# 3_waffling60-NMB_mcu.net
KiCad netlist of a schematic drawn in Altium Designer
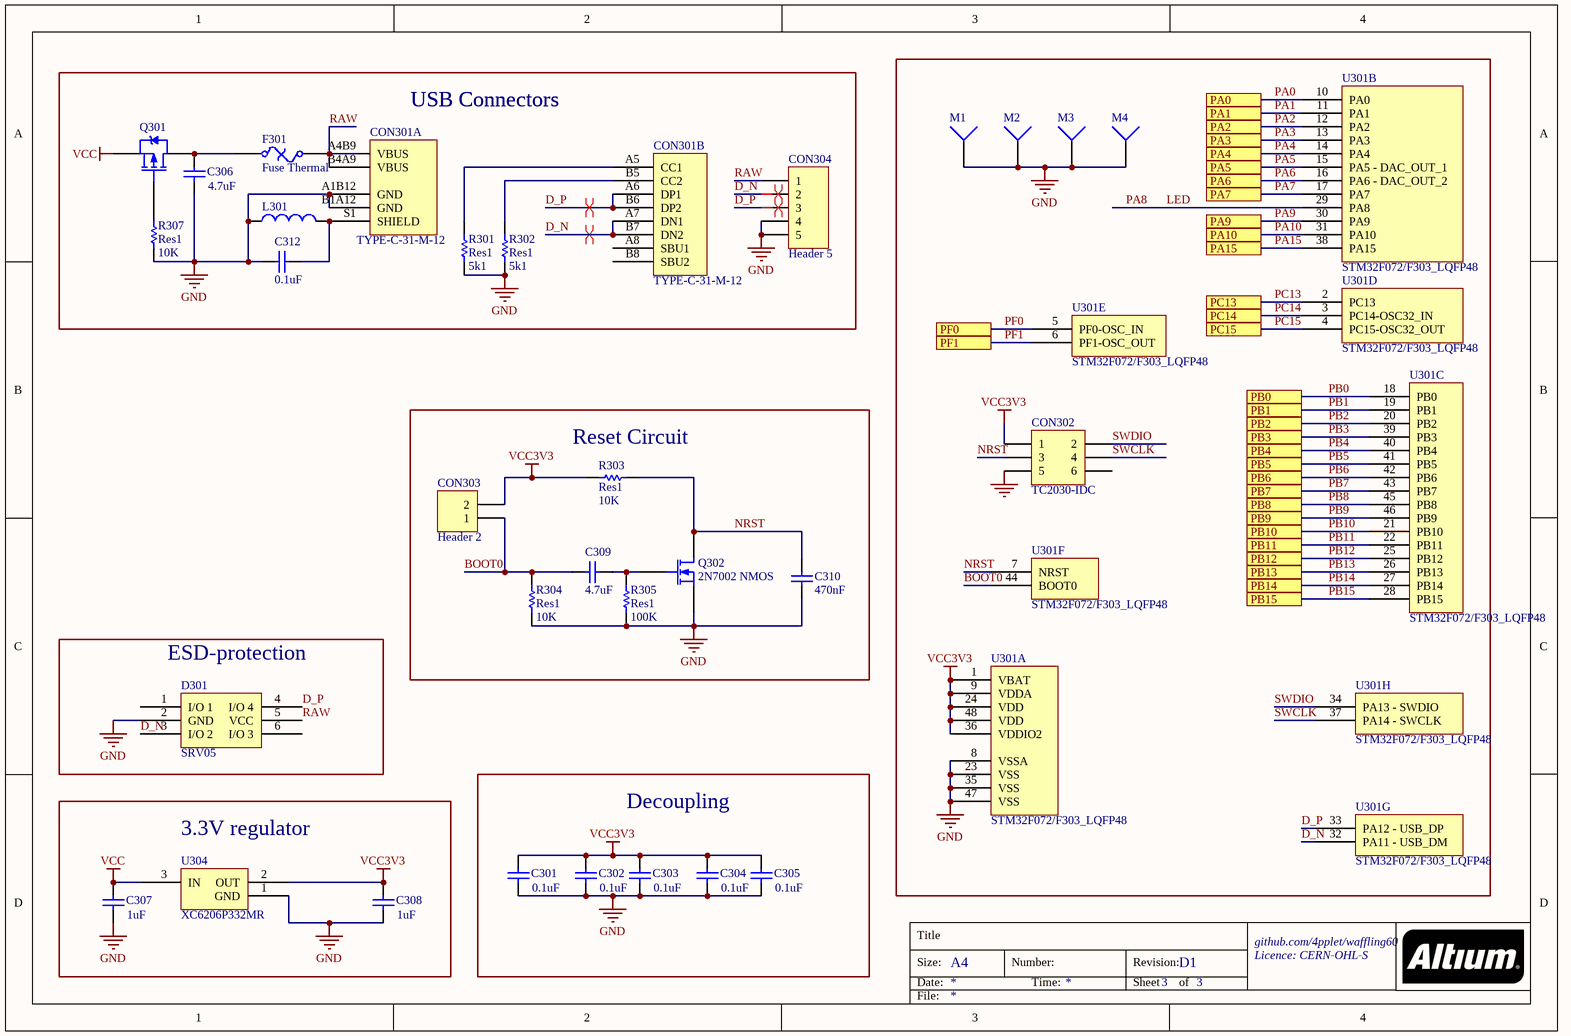
[diagram p0: 3_waffling60-NMB_mcu.SchDoc]

(export (version "E")
  (design (tool "Eeschema 10.0.6"))
  (components
    (comp (ref "C301")
      (value "0.1uF")
      (footprint "C0603[1608]")
      (description "Capacitor")
      (fields (field (name "LCSC PART #") "C14663") (field (name "MRF.PART") "CC0603KRX7R9BB104"))
      (libsource (lib "Miscellaneous Devices") (part "Cap"))
    )
    (comp (ref "C302")
      (value "0.1uF")
      (footprint "C0603[1608]")
      (description "Capacitor")
      (fields (field (name "LCSC PART #") "C14663") (field (name "MRF.PART") "CC0603KRX7R9BB104"))
      (libsource (lib "Miscellaneous Devices") (part "Cap"))
    )
    (comp (ref "C303")
      (value "0.1uF")
      (footprint "C0603[1608]")
      (description "Capacitor")
      (fields (field (name "LCSC PART #") "C14663") (field (name "MRF.PART") "CC0603KRX7R9BB104"))
      (libsource (lib "Miscellaneous Devices") (part "Cap"))
    )
    (comp (ref "C304")
      (value "0.1uF")
      (footprint "C0603[1608]")
      (description "Capacitor")
      (fields (field (name "LCSC PART #") "C14663") (field (name "MRF.PART") "CC0603KRX7R9BB104"))
      (libsource (lib "Miscellaneous Devices") (part "Cap"))
    )
    (comp (ref "C305")
      (value "0.1uF")
      (footprint "C0603[1608]")
      (description "Capacitor")
      (fields (field (name "LCSC PART #") "C14663") (field (name "MRF.PART") "CC0603KRX7R9BB104"))
      (libsource (lib "Miscellaneous Devices") (part "Cap"))
    )
    (comp (ref "C306")
      (value "4.7uF")
      (footprint "C0603[1608]")
      (description "Capacitor")
      (fields (field (name "LCSC PART #") "C19666") (field (name "MRF.PART") "CL10A475KO8NNNC"))
      (libsource (lib "Miscellaneous Devices") (part "Cap"))
    )
    (comp (ref "C307")
      (value "1uF")
      (footprint "C0603[1608]")
      (description "Capacitor")
      (fields (field (name "LCSC PART #") "C15849") (field (name "MRF.PART") "CL10A105KB8NNNC"))
      (libsource (lib "Miscellaneous Devices") (part "Cap"))
    )
    (comp (ref "C308")
      (value "1uF")
      (footprint "C0603[1608]")
      (description "Capacitor")
      (fields (field (name "LCSC PART #") "C15849") (field (name "MRF.PART") "CL10A105KB8NNNC"))
      (libsource (lib "Miscellaneous Devices") (part "Cap"))
    )
    (comp (ref "C309")
      (value "4.7uF")
      (footprint "C0603[1608]")
      (description "Capacitor")
      (fields (field (name "LCSC PART #") "C19666") (field (name "MRF.PART") "CL10A475KO8NNNC"))
      (libsource (lib "Miscellaneous Devices") (part "Cap"))
    )
    (comp (ref "C310")
      (value "470nF")
      (footprint "C0603[1608]")
      (description "Capacitor")
      (fields (field (name "LCSC PART #") "C1623") (field (name "MRF.PART") "CL10B474KA8NNNC"))
      (libsource (lib "Miscellaneous Devices") (part "Cap"))
    )
    (comp (ref "C312")
      (value "0.1uF")
      (footprint "C0603[1608]")
      (description "Capacitor")
      (fields (field (name "LCSC PART #") "C14663") (field (name "MRF.PART") "CC0603KRX7R9BB104"))
      (libsource (lib "Miscellaneous Devices") (part "Cap"))
    )
    (comp (ref "CON301")
      (value "TYPE-C-31-M-12")
      (footprint "TYPE-C-31-M-12")
      (fields (field (name "LCSC PART #") "C165948"))
      (libsource (lib "Schlib1") (part "TYPE-C-31-M-12"))
    )
    (comp (ref "CON302")
      (value "TC2030-IDC")
      (footprint "TC2030-IDC-NL")
      (description "Header, 3-Pin, Dual row")
      (libsource (lib "Miscellaneous Connectors") (part "Header 3X2"))
    )
    (comp (ref "CON303")
      (value "Header 2")
      (footprint "HDR1X2")
      (description "Header, 2-Pin")
      (libsource (lib "Miscellaneous Connectors") (part "Header 2"))
    )
    (comp (ref "CON304")
      (value "Header 5")
      (footprint "Molex 781710004")
      (description "JST for USB daughter board")
      (fields (field (name "LCSC PART #") "C2840019") (field (name "MRF.PART") "M1201RS-04-BK"))
      (libsource (lib "Miscellaneous Connectors") (part "Header 5"))
    )
    (comp (ref "D301")
      (value "SRV05")
      (footprint "SOT-23-6")
      (fields (field (name "LCSC PART #") "C85364") (field (name "MRF.PART") "SRV05-4-P-T7"))
      (libsource (lib "Keebs") (part "SRV05"))
    )
    (comp (ref "F301")
      (value "Fuse Thermal")
      (footprint "C1206[3216]")
      (description "Thermal Fuse")
      (fields (field (name "LCSC PART #") "C135338") (field (name "MRF.PART") "ASMD1206-050"))
      (libsource (lib "Miscellaneous Devices") (part "Fuse Thermal"))
    )
    (comp (ref "L301")
      (value "Inductor")
      (footprint "L0805")
      (fields (field (name "LCSC PART #") "C1015") (field (name "MRF.PART") "GZ2012D101TF"))
      (libsource (lib "Simulation Generic Components") (part "Inductor"))
    )
    (comp (ref "M1")
      (value "Socket")
      (footprint "mounting_hole")
      (libsource (lib "Miscellaneous Connectors") (part "Socket"))
    )
    (comp (ref "M2")
      (value "Socket")
      (footprint "mounting_hole")
      (libsource (lib "Miscellaneous Connectors") (part "Socket"))
    )
    (comp (ref "M3")
      (value "Socket")
      (footprint "mounting_hole")
      (libsource (lib "Miscellaneous Connectors") (part "Socket"))
    )
    (comp (ref "M4")
      (value "Socket")
      (footprint "mounting_hole")
      (libsource (lib "Miscellaneous Connectors") (part "Socket"))
    )
    (comp (ref "Q301")
      (value "PMOS-2")
      (footprint "SOT-23-3")
      (description "P-Channel Power MOSFET")
      (fields (field (name "LCSC PART #") "C10487") (field (name "MRF.PART") "SI2301CDS-T1-GE3"))
      (libsource (lib "Miscellaneous Devices") (part "PMOS-2"))
    )
    (comp (ref "Q302")
      (value "2N7002 NMOS")
      (footprint "SOT-23-3")
      (description "N-Channel MOSFET")
      (fields (field (name "LCSC PART #") "C8545") (field (name "MRF.PART") "2N7002"))
      (libsource (lib "Miscellaneous Devices") (part "MOSFET-N"))
    )
    (comp (ref "R301")
      (value "Res1")
      (footprint "R0603[1608]")
      (description "Resistor")
      (fields
        (field (name "ALTIUM_VALUE") "5k1")
        (field (name "LCSC PART #") "C23186")
        (field (name "MRF.PART") "0603WAF5101T5E")
      )
      (libsource (lib "Miscellaneous Devices") (part "Res1"))
    )
    (comp (ref "R302")
      (value "Res1")
      (footprint "R0603[1608]")
      (description "Resistor")
      (fields
        (field (name "ALTIUM_VALUE") "5k1")
        (field (name "LCSC PART #") "C23186")
        (field (name "MRF.PART") "0603WAF5101T5E")
      )
      (libsource (lib "Miscellaneous Devices") (part "Res1"))
    )
    (comp (ref "R303")
      (value "Res1")
      (footprint "R0603[1608]")
      (description "Resistor")
      (fields
        (field (name "ALTIUM_VALUE") "10K")
        (field (name "LCSC PART #") "C25804")
        (field (name "MRF.PART") "0603WAF1002T5E")
      )
      (libsource (lib "Miscellaneous Devices") (part "Res1"))
    )
    (comp (ref "R304")
      (value "Res1")
      (footprint "R0603[1608]")
      (description "Resistor")
      (fields
        (field (name "ALTIUM_VALUE") "10K")
        (field (name "LCSC PART #") "C25804")
        (field (name "MRF.PART") "0603WAF1002T5E")
      )
      (libsource (lib "Miscellaneous Devices") (part "Res1"))
    )
    (comp (ref "R305")
      (value "Res1")
      (footprint "R0603[1608]")
      (description "Resistor")
      (fields
        (field (name "ALTIUM_VALUE") "100K")
        (field (name "LCSC PART #") "C25803")
        (field (name "MRF.PART") "0603WAF1003T5E")
      )
      (libsource (lib "Miscellaneous Devices") (part "Res1"))
    )
    (comp (ref "R307")
      (value "Res1")
      (footprint "R0603[1608]")
      (description "Resistor")
      (fields
        (field (name "ALTIUM_VALUE") "10K")
        (field (name "LCSC PART #") "C25804")
        (field (name "MRF.PART") "0603WAF1002T5E")
      )
      (libsource (lib "Miscellaneous Devices") (part "Res1"))
    )
    (comp (ref "U301")
      (value "STM32F072/F303_LQFP48")
      (footprint "STM32 - COMBO 7X7MM")
      (fields (field (name "LCSC PART #") "C915660") (field (name "MRF.PART") "APM32F072CBT6"))
      (libsource (lib "Keebs") (part "STM32F072/F303_LQFP48"))
    )
    (comp (ref "U304")
      (value "XC6206P332MR")
      (footprint "SOT-23-3")
      (fields (field (name "LCSC PART #") "C5446"))
      (libsource (lib "Keebs") (part "SOT23 LDO"))
    )
  )
  (nets
    (net (code "1") (name "/BOOT0") (class "Default")
      (node (ref "C309") (pin "1") (pinfunction "1_1") (pintype "passive"))
      (node (ref "CON303") (pin "1") (pinfunction "1_1") (pintype "passive"))
      (node (ref "R304") (pin "1") (pinfunction "1_1") (pintype "passive"))
      (node (ref "U301") (pin "44") (pinfunction "BOOT0_44") (pintype "passive"))
    )
    (net (code "2") (name "/D_N") (class "Default")
      (node (ref "CON301") (pin "A7") (pinfunction "DN1_A7") (pintype "passive"))
      (node (ref "CON301") (pin "B7") (pinfunction "DN2_B7") (pintype "passive"))
      (node (ref "CON304") (pin "2") (pinfunction "2_2") (pintype "passive"))
      (node (ref "D301") (pin "3") (pinfunction "I/O_2_3") (pintype "passive"))
      (node (ref "U301") (pin "32") (pinfunction "PA11_-_USB_DM_32") (pintype "passive"))
    )
    (net (code "3") (name "/D_P") (class "Default")
      (node (ref "CON301") (pin "A6") (pinfunction "DP1_A6") (pintype "passive"))
      (node (ref "CON301") (pin "B6") (pinfunction "DP2_B6") (pintype "passive"))
      (node (ref "CON304") (pin "3") (pinfunction "3_3") (pintype "passive"))
      (node (ref "D301") (pin "4") (pinfunction "I/O_4_4") (pintype "passive"))
      (node (ref "U301") (pin "33") (pinfunction "PA12_-_USB_DP_33") (pintype "passive"))
    )
    (net (code "4") (name "/LED") (class "Default")
      (node (ref "U301") (pin "29") (pinfunction "PA8_29") (pintype "passive"))
    )
    (net (code "5") (name "/NRST") (class "Default")
      (node (ref "C310") (pin "1") (pinfunction "1_1") (pintype "passive"))
      (node (ref "CON302") (pin "3") (pinfunction "3_3") (pintype "passive"))
      (node (ref "Q302") (pin "3") (pinfunction "D_3") (pintype "passive"))
      (node (ref "R303") (pin "2") (pinfunction "2_2") (pintype "passive"))
      (node (ref "U301") (pin "7") (pinfunction "NRST_7") (pintype "passive"))
    )
    (net (code "6") (name "/PA0") (class "Default")
      (node (ref "U301") (pin "10") (pinfunction "PA0_10") (pintype "passive"))
    )
    (net (code "7") (name "/PA1") (class "Default")
      (node (ref "U301") (pin "11") (pinfunction "PA1_11") (pintype "passive"))
    )
    (net (code "8") (name "/PA2") (class "Default")
      (node (ref "U301") (pin "12") (pinfunction "PA2_12") (pintype "passive"))
    )
    (net (code "9") (name "/PA3") (class "Default")
      (node (ref "U301") (pin "13") (pinfunction "PA3_13") (pintype "passive"))
    )
    (net (code "10") (name "/PA4") (class "Default")
      (node (ref "U301") (pin "14") (pinfunction "PA4_14") (pintype "passive"))
    )
    (net (code "11") (name "/PA5") (class "Default")
      (node (ref "U301") (pin "15") (pinfunction "PA5_-_DAC_OUT_1_15") (pintype "passive"))
    )
    (net (code "12") (name "/PA6") (class "Default")
      (node (ref "U301") (pin "16") (pinfunction "PA6_-_DAC_OUT_2_16") (pintype "passive"))
    )
    (net (code "13") (name "/PA7") (class "Default")
      (node (ref "U301") (pin "17") (pinfunction "PA7_17") (pintype "passive"))
    )
    (net (code "14") (name "/PA9") (class "Default")
      (node (ref "U301") (pin "30") (pinfunction "PA9_30") (pintype "passive"))
    )
    (net (code "15") (name "/PA10") (class "Default")
      (node (ref "U301") (pin "31") (pinfunction "PA10_31") (pintype "passive"))
    )
    (net (code "16") (name "/PA15") (class "Default")
      (node (ref "U301") (pin "38") (pinfunction "PA15_38") (pintype "passive"))
    )
    (net (code "17") (name "/PB0") (class "Default")
      (node (ref "U301") (pin "18") (pinfunction "PB0_18") (pintype "passive"))
    )
    (net (code "18") (name "/PB1") (class "Default")
      (node (ref "U301") (pin "19") (pinfunction "PB1_19") (pintype "passive"))
    )
    (net (code "19") (name "/PB2") (class "Default")
      (node (ref "U301") (pin "20") (pinfunction "PB2_20") (pintype "passive"))
    )
    (net (code "20") (name "/PB3") (class "Default")
      (node (ref "U301") (pin "39") (pinfunction "PB3_39") (pintype "passive"))
    )
    (net (code "21") (name "/PB4") (class "Default")
      (node (ref "U301") (pin "40") (pinfunction "PB4_40") (pintype "passive"))
    )
    (net (code "22") (name "/PB5") (class "Default")
      (node (ref "U301") (pin "41") (pinfunction "PB5_41") (pintype "passive"))
    )
    (net (code "23") (name "/PB6") (class "Default")
      (node (ref "U301") (pin "42") (pinfunction "PB6_42") (pintype "passive"))
    )
    (net (code "24") (name "/PB7") (class "Default")
      (node (ref "U301") (pin "43") (pinfunction "PB7_43") (pintype "passive"))
    )
    (net (code "25") (name "/PB8") (class "Default")
      (node (ref "U301") (pin "45") (pinfunction "PB8_45") (pintype "passive"))
    )
    (net (code "26") (name "/PB9") (class "Default")
      (node (ref "U301") (pin "46") (pinfunction "PB9_46") (pintype "passive"))
    )
    (net (code "27") (name "/PB10") (class "Default")
      (node (ref "U301") (pin "21") (pinfunction "PB10_21") (pintype "passive"))
    )
    (net (code "28") (name "/PB11") (class "Default")
      (node (ref "U301") (pin "22") (pinfunction "PB11_22") (pintype "passive"))
    )
    (net (code "29") (name "/PB12") (class "Default")
      (node (ref "U301") (pin "25") (pinfunction "PB12_25") (pintype "passive"))
    )
    (net (code "30") (name "/PB13") (class "Default")
      (node (ref "U301") (pin "26") (pinfunction "PB13_26") (pintype "passive"))
    )
    (net (code "31") (name "/PB14") (class "Default")
      (node (ref "U301") (pin "27") (pinfunction "PB14_27") (pintype "passive"))
    )
    (net (code "32") (name "/PB15") (class "Default")
      (node (ref "U301") (pin "28") (pinfunction "PB15_28") (pintype "passive"))
    )
    (net (code "33") (name "/PC13") (class "Default")
      (node (ref "U301") (pin "2") (pinfunction "PC13_2") (pintype "passive"))
    )
    (net (code "34") (name "/PC14") (class "Default")
      (node (ref "U301") (pin "3") (pinfunction "PC14-OSC32_IN_3") (pintype "passive"))
    )
    (net (code "35") (name "/PC15") (class "Default")
      (node (ref "U301") (pin "4") (pinfunction "PC15-OSC32_OUT_4") (pintype "passive"))
    )
    (net (code "36") (name "/PF0") (class "Default")
      (node (ref "U301") (pin "5") (pinfunction "PF0-OSC_IN_5") (pintype "passive"))
    )
    (net (code "37") (name "/PF1") (class "Default")
      (node (ref "U301") (pin "6") (pinfunction "PF1-OSC_OUT_6") (pintype "passive"))
    )
    (net (code "38") (name "/RAW") (class "Default")
      (node (ref "CON301") (pin "A4B9") (pinfunction "VBUS_A4B9") (pintype "passive"))
      (node (ref "CON301") (pin "B4A9") (pinfunction "VBUS_B4A9") (pintype "passive"))
      (node (ref "CON304") (pin "1") (pinfunction "1_1") (pintype "passive"))
      (node (ref "D301") (pin "5") (pinfunction "VCC_5") (pintype "passive"))
      (node (ref "F301") (pin "2") (pinfunction "2_2") (pintype "passive"))
    )
    (net (code "39") (name "/SWCLK") (class "Default")
      (node (ref "CON302") (pin "4") (pinfunction "4_4") (pintype "passive"))
      (node (ref "U301") (pin "37") (pinfunction "PA14_-_SWCLK_37") (pintype "passive"))
    )
    (net (code "40") (name "/SWDIO") (class "Default")
      (node (ref "CON302") (pin "2") (pinfunction "2_2") (pintype "passive"))
      (node (ref "U301") (pin "34") (pinfunction "PA13_-_SWDIO_34") (pintype "passive"))
    )
    (net (code "41") (name "GND") (class "Default")
      (node (ref "C301") (pin "1") (pinfunction "1_1") (pintype "passive"))
      (node (ref "C302") (pin "1") (pinfunction "1_1") (pintype "passive"))
      (node (ref "C303") (pin "1") (pinfunction "1_1") (pintype "passive"))
      (node (ref "C304") (pin "1") (pinfunction "1_1") (pintype "passive"))
      (node (ref "C305") (pin "1") (pinfunction "1_1") (pintype "passive"))
      (node (ref "C306") (pin "1") (pinfunction "1_1") (pintype "passive"))
      (node (ref "C307") (pin "1") (pinfunction "1_1") (pintype "passive"))
      (node (ref "C308") (pin "1") (pinfunction "1_1") (pintype "passive"))
      (node (ref "C310") (pin "2") (pinfunction "2_2") (pintype "passive"))
      (node (ref "C312") (pin "1") (pinfunction "1_1") (pintype "passive"))
      (node (ref "CON301") (pin "A1B12") (pinfunction "GND_A1B12") (pintype "passive"))
      (node (ref "CON301") (pin "B1A12") (pinfunction "GND_B1A12") (pintype "passive"))
      (node (ref "CON302") (pin "5") (pinfunction "5_5") (pintype "passive"))
      (node (ref "CON304") (pin "4") (pinfunction "4_4") (pintype "passive"))
      (node (ref "CON304") (pin "5") (pinfunction "5_5") (pintype "passive"))
      (node (ref "D301") (pin "2") (pinfunction "GND_2") (pintype "passive"))
      (node (ref "L301") (pin "1") (pinfunction "1_1") (pintype "passive"))
      (node (ref "M1") (pin "1") (pinfunction "1_1") (pintype "passive"))
      (node (ref "M2") (pin "1") (pinfunction "1_1") (pintype "passive"))
      (node (ref "M3") (pin "1") (pinfunction "1_1") (pintype "passive"))
      (node (ref "M4") (pin "1") (pinfunction "1_1") (pintype "passive"))
      (node (ref "Q302") (pin "2") (pinfunction "S_2") (pintype "passive"))
      (node (ref "R301") (pin "2") (pinfunction "2_2") (pintype "passive"))
      (node (ref "R302") (pin "2") (pinfunction "2_2") (pintype "passive"))
      (node (ref "R304") (pin "2") (pinfunction "2_2") (pintype "passive"))
      (node (ref "R305") (pin "2") (pinfunction "2_2") (pintype "passive"))
      (node (ref "R307") (pin "2") (pinfunction "2_2") (pintype "passive"))
      (node (ref "U301") (pin "23") (pinfunction "VSS_23") (pintype "passive"))
      (node (ref "U301") (pin "35") (pinfunction "VSS_35") (pintype "passive"))
      (node (ref "U301") (pin "47") (pinfunction "VSS_47") (pintype "passive"))
      (node (ref "U301") (pin "8") (pinfunction "VSSA_8") (pintype "passive"))
      (node (ref "U304") (pin "1") (pinfunction "GND_1") (pintype "passive"))
    )
    (net (code "42") (name "Net-(CON301A-SHIELD)") (class "Default")
      (node (ref "C312") (pin "2") (pinfunction "2_2") (pintype "passive"))
      (node (ref "CON301") (pin "S1") (pinfunction "SHIELD_S1") (pintype "passive"))
      (node (ref "L301") (pin "2") (pinfunction "2_2") (pintype "passive"))
    )
    (net (code "43") (name "Net-(CON301B-CC1)") (class "Default")
      (node (ref "CON301") (pin "A5") (pinfunction "CC1_A5") (pintype "passive"))
      (node (ref "R301") (pin "1") (pinfunction "1_1") (pintype "passive"))
    )
    (net (code "44") (name "Net-(CON301B-CC2)") (class "Default")
      (node (ref "CON301") (pin "B5") (pinfunction "CC2_B5") (pintype "passive"))
      (node (ref "R302") (pin "1") (pinfunction "1_1") (pintype "passive"))
    )
    (net (code "45") (name "Net-(Q301-D)") (class "Default")
      (node (ref "C306") (pin "2") (pinfunction "2_2") (pintype "passive"))
      (node (ref "F301") (pin "1") (pinfunction "1_1") (pintype "passive"))
      (node (ref "Q301") (pin "3") (pinfunction "D_3") (pintype "passive"))
    )
    (net (code "46") (name "Net-(Q301-G)") (class "Default")
      (node (ref "Q301") (pin "1") (pinfunction "G_1") (pintype "passive"))
      (node (ref "R307") (pin "1") (pinfunction "1_1") (pintype "passive"))
    )
    (net (code "47") (name "Net-(Q302-G)") (class "Default")
      (node (ref "C309") (pin "2") (pinfunction "2_2") (pintype "passive"))
      (node (ref "Q302") (pin "1") (pinfunction "G_1") (pintype "passive"))
      (node (ref "R305") (pin "1") (pinfunction "1_1") (pintype "passive"))
    )
    (net (code "48") (name "VCC") (class "Default")
      (node (ref "C307") (pin "2") (pinfunction "2_2") (pintype "passive"))
      (node (ref "Q301") (pin "2") (pinfunction "S_2") (pintype "passive"))
      (node (ref "U304") (pin "3") (pinfunction "IN_3") (pintype "passive"))
    )
    (net (code "49") (name "VCC3V3") (class "Default")
      (node (ref "C301") (pin "2") (pinfunction "2_2") (pintype "passive"))
      (node (ref "C302") (pin "2") (pinfunction "2_2") (pintype "passive"))
      (node (ref "C303") (pin "2") (pinfunction "2_2") (pintype "passive"))
      (node (ref "C304") (pin "2") (pinfunction "2_2") (pintype "passive"))
      (node (ref "C305") (pin "2") (pinfunction "2_2") (pintype "passive"))
      (node (ref "C308") (pin "2") (pinfunction "2_2") (pintype "passive"))
      (node (ref "CON302") (pin "1") (pinfunction "1_1") (pintype "passive"))
      (node (ref "CON303") (pin "2") (pinfunction "2_2") (pintype "passive"))
      (node (ref "R303") (pin "1") (pinfunction "1_1") (pintype "passive"))
      (node (ref "U301") (pin "1") (pinfunction "VBAT_1") (pintype "passive"))
      (node (ref "U301") (pin "24") (pinfunction "VDD_24") (pintype "passive"))
      (node (ref "U301") (pin "36") (pinfunction "VDDIO2_36") (pintype "passive"))
      (node (ref "U301") (pin "48") (pinfunction "VDD_48") (pintype "passive"))
      (node (ref "U301") (pin "9") (pinfunction "VDDA_9") (pintype "passive"))
      (node (ref "U304") (pin "2") (pinfunction "OUT_2") (pintype "passive"))
    )
    (net (code "50") (name "unconnected-(CON301B-SBU1-PadA8)") (class "Default")
      (node (ref "CON301") (pin "A8") (pinfunction "SBU1_A8") (pintype "passive"))
    )
    (net (code "51") (name "unconnected-(CON301B-SBU2-PadB8)") (class "Default")
      (node (ref "CON301") (pin "B8") (pinfunction "SBU2_B8") (pintype "passive"))
    )
    (net (code "52") (name "unconnected-(CON302-Pad6)") (class "Default")
      (node (ref "CON302") (pin "6") (pinfunction "6_6") (pintype "passive"))
    )
    (net (code "53") (name "unconnected-(D301-I{slash}O_1-Pad1)") (class "Default")
      (node (ref "D301") (pin "1") (pinfunction "I/O_1_1") (pintype "passive"))
    )
    (net (code "54") (name "unconnected-(D301-I{slash}O_3-Pad6)") (class "Default")
      (node (ref "D301") (pin "6") (pinfunction "I/O_3_6") (pintype "passive"))
    )
  )
)
